# counter-defender-featherwing-mk-1_0.net
KiCad netlist of a schematic drawn in EAGLE
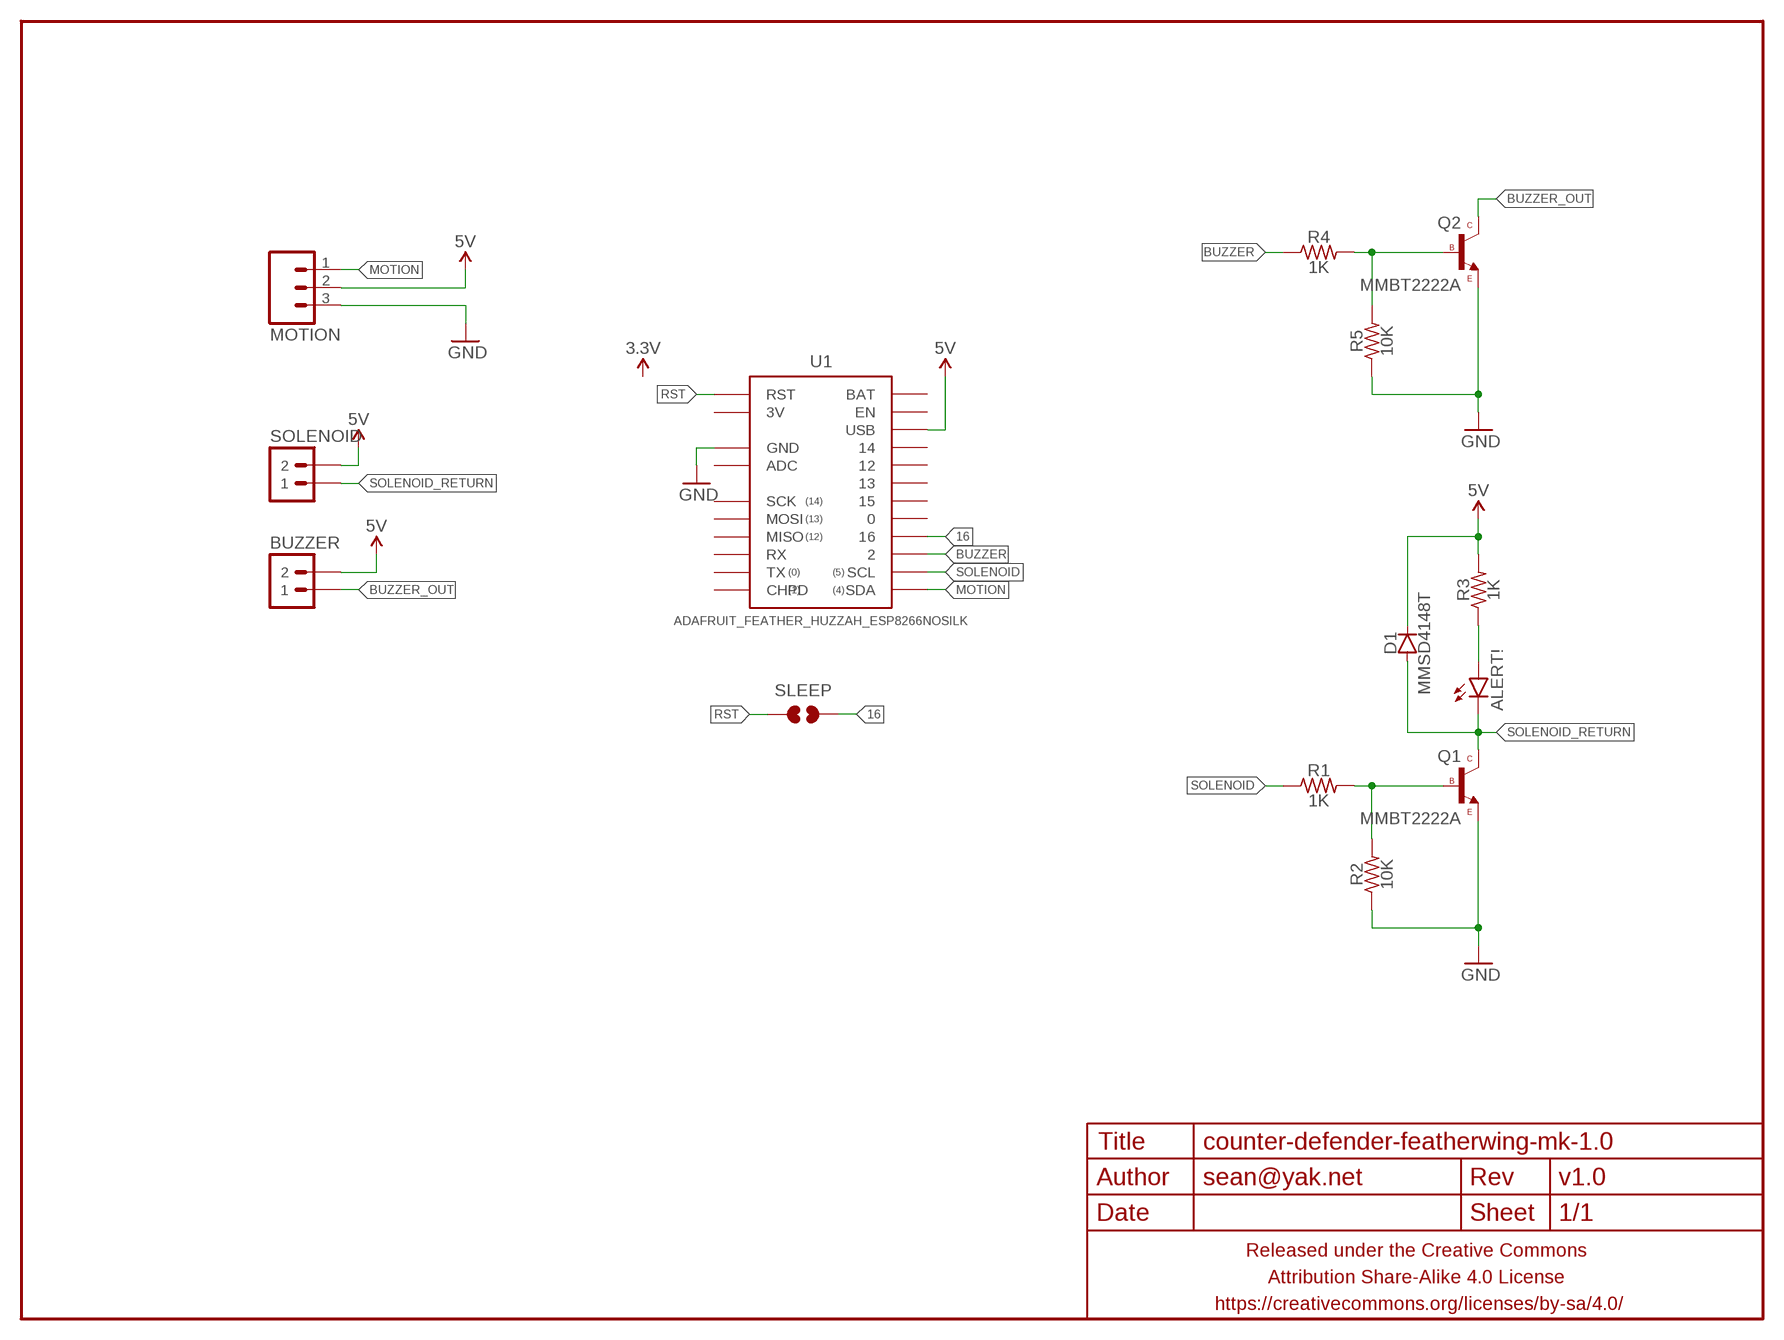
[diagram p0: schematic, sheet 1]

(export (version "E")
  (design (tool "Eeschema 10.0.6"))
  (components
    (comp (ref "ALERT!")
      (value "LED0603-TIGHT")
      (footprint "eagle-import:LED-0603-TIGHT")
      (libsource (lib "eagle-import") (part "LED0603-TIGHT"))
    )
    (comp (ref "BUZZER")
      (value "M02JST-PTH-RA-SMALLPADS")
      (footprint "eagle-import:JST-2-PH-RA-PTH-SMALLPADS")
      (libsource (lib "eagle-import") (part "M02JST-PTH-RA-SMALLPADS"))
    )
    (comp (ref "D1")
      (value "MMSD4148T")
      (footprint "eagle-import:SOD123")
      (libsource (lib "eagle-import") (part "DIODESOD123"))
    )
    (comp (ref "FRAME1")
      (value "FRAME-LETTERNO_PACKAGE")
      (footprint "eagle-import:DUMMY")
      (fields (field (name "DESIGNER") "sean@yak.net") (field (name "VERSION") "v1.0"))
      (libsource (lib "eagle-import") (part "FRAME-LETTERNO_PACKAGE"))
    )
    (comp (ref "MOTION")
      (value "M03JST-PTH")
      (footprint "eagle-import:JST-3-PH-RA-PTH")
      (libsource (lib "eagle-import") (part "M03JST-PTH"))
    )
    (comp (ref "Q1")
      (value "MMBT2222A")
      (footprint "eagle-import:SOT23")
      (libsource (lib "eagle-import") (part "TRANSISTOR_NPNMMBT2222A"))
    )
    (comp (ref "Q2")
      (value "MMBT2222A")
      (footprint "eagle-import:SOT23")
      (libsource (lib "eagle-import") (part "TRANSISTOR_NPNMMBT2222A"))
    )
    (comp (ref "R1")
      (value "1K")
      (footprint "eagle-import:R0603-TIGHTER")
      (libsource (lib "eagle-import") (part "RESISTORR0603-TIGHTER"))
    )
    (comp (ref "R2")
      (value "10K")
      (footprint "eagle-import:R0603-TIGHTER")
      (libsource (lib "eagle-import") (part "RESISTORR0603-TIGHTER"))
    )
    (comp (ref "R3")
      (value "1K")
      (footprint "eagle-import:R0603-TIGHTER")
      (libsource (lib "eagle-import") (part "RESISTORR0603-TIGHTER"))
    )
    (comp (ref "R4")
      (value "1K")
      (footprint "eagle-import:R0603-TIGHTER")
      (libsource (lib "eagle-import") (part "RESISTORR0603-TIGHTER"))
    )
    (comp (ref "R5")
      (value "10K")
      (footprint "eagle-import:R0603-TIGHTER")
      (libsource (lib "eagle-import") (part "RESISTORR0603-TIGHTER"))
    )
    (comp (ref "SLEEP")
      (value "JUMPER-PAD-2-NOYES_SILK")
      (footprint "eagle-import:PAD-JUMPER-2-NO_YES_SILK")
      (libsource (lib "eagle-import") (part "JUMPER-PAD-2-NOYES_SILK"))
    )
    (comp (ref "SOLENOID")
      (value "M02JST-PTH-RA-SMALLPADS")
      (footprint "eagle-import:JST-2-PH-RA-PTH-SMALLPADS")
      (libsource (lib "eagle-import") (part "M02JST-PTH-RA-SMALLPADS"))
    )
    (comp (ref "U1")
      (value "ADAFRUIT_FEATHER_HUZZAH_ESP8266NOSILK")
      (footprint "eagle-import:ADAFRUIT_FEATHER_HUZZAH_NOSILK")
      (libsource (lib "eagle-import") (part "ADAFRUIT_FEATHER_HUZZAH_ESP8266NOSILK"))
    )
  )
  (nets
    (net (code "2") (name "5V") (class "Default")
      (node (ref "BUZZER") (pin "2") (pinfunction "2_2") (pintype "passive"))
      (node (ref "D1") (pin "C") (pinfunction "C_C") (pintype "passive"))
      (node (ref "MOTION") (pin "2") (pinfunction "2_2") (pintype "passive"))
      (node (ref "R3") (pin "2") (pinfunction "2_2") (pintype "passive"))
      (node (ref "SOLENOID") (pin "2") (pinfunction "2_2") (pintype "passive"))
      (node (ref "U1") (pin "USB") (pinfunction "USB_USB") (pintype "bidirectional"))
    )
    (net (code "3") (name "16") (class "Default")
      (node (ref "SLEEP") (pin "2") (pinfunction "2_2") (pintype "passive"))
      (node (ref "U1") (pin "16") (pinfunction "16_16") (pintype "bidirectional"))
    )
    (net (code "4") (name "BUZZER") (class "Default")
      (node (ref "R4") (pin "1") (pinfunction "1_1") (pintype "passive"))
      (node (ref "U1") (pin "2") (pinfunction "2_2") (pintype "bidirectional"))
    )
    (net (code "5") (name "BUZZER_OUT") (class "Default")
      (node (ref "BUZZER") (pin "1") (pinfunction "1_1") (pintype "passive"))
      (node (ref "Q2") (pin "3") (pinfunction "C_3") (pintype "passive"))
    )
    (net (code "6") (name "GND") (class "Default")
      (node (ref "MOTION") (pin "3") (pinfunction "3_3") (pintype "passive"))
      (node (ref "Q1") (pin "2") (pinfunction "E_2") (pintype "passive"))
      (node (ref "Q2") (pin "2") (pinfunction "E_2") (pintype "passive"))
      (node (ref "R2") (pin "1") (pinfunction "1_1") (pintype "passive"))
      (node (ref "R5") (pin "1") (pinfunction "1_1") (pintype "passive"))
      (node (ref "U1") (pin "GND@0") (pinfunction "GND_GND@0") (pintype "bidirectional"))
    )
    (net (code "7") (name "MOTION") (class "Default")
      (node (ref "MOTION") (pin "1") (pinfunction "1_1") (pintype "passive"))
      (node (ref "U1") (pin "SDA") (pinfunction "SDA_SDA") (pintype "bidirectional"))
    )
    (net (code "8") (name "Net-(ALERT!-PadA)") (class "Default")
      (node (ref "ALERT!") (pin "A") (pinfunction "A_A") (pintype "passive"))
      (node (ref "R3") (pin "1") (pinfunction "1_1") (pintype "passive"))
    )
    (net (code "9") (name "Net-(Q1-B)") (class "Default")
      (node (ref "Q1") (pin "1") (pinfunction "B_1") (pintype "passive"))
      (node (ref "R1") (pin "2") (pinfunction "2_2") (pintype "passive"))
      (node (ref "R2") (pin "2") (pinfunction "2_2") (pintype "passive"))
    )
    (net (code "10") (name "Net-(Q2-B)") (class "Default")
      (node (ref "Q2") (pin "1") (pinfunction "B_1") (pintype "passive"))
      (node (ref "R4") (pin "2") (pinfunction "2_2") (pintype "passive"))
      (node (ref "R5") (pin "2") (pinfunction "2_2") (pintype "passive"))
    )
    (net (code "11") (name "RST") (class "Default")
      (node (ref "SLEEP") (pin "1") (pinfunction "1_1") (pintype "passive"))
      (node (ref "U1") (pin "RST") (pinfunction "RST_RST") (pintype "bidirectional"))
    )
    (net (code "12") (name "SOLENOID") (class "Default")
      (node (ref "R1") (pin "1") (pinfunction "1_1") (pintype "passive"))
      (node (ref "U1") (pin "SCL") (pinfunction "SCL_SCL") (pintype "bidirectional"))
    )
    (net (code "13") (name "SOLENOID_RETURN") (class "Default")
      (node (ref "ALERT!") (pin "C") (pinfunction "C_C") (pintype "passive"))
      (node (ref "D1") (pin "A") (pinfunction "A_A") (pintype "passive"))
      (node (ref "Q1") (pin "3") (pinfunction "C_3") (pintype "passive"))
      (node (ref "SOLENOID") (pin "1") (pinfunction "1_1") (pintype "passive"))
    )
    (net (code "14") (name "unconnected-(U1-Pad0)") (class "Default")
      (node (ref "U1") (pin "0") (pinfunction "0_0") (pintype "bidirectional"))
    )
    (net (code "15") (name "unconnected-(U1-Pad3V)") (class "Default")
      (node (ref "U1") (pin "3V") (pinfunction "3V_3V") (pintype "bidirectional"))
    )
    (net (code "16") (name "unconnected-(U1-Pad12)") (class "Default")
      (node (ref "U1") (pin "12") (pinfunction "12_12") (pintype "bidirectional"))
    )
    (net (code "17") (name "unconnected-(U1-Pad13)") (class "Default")
      (node (ref "U1") (pin "13") (pinfunction "13_13") (pintype "bidirectional"))
    )
    (net (code "18") (name "unconnected-(U1-Pad14)") (class "Default")
      (node (ref "U1") (pin "14") (pinfunction "14_14") (pintype "bidirectional"))
    )
    (net (code "19") (name "unconnected-(U1-Pad15)") (class "Default")
      (node (ref "U1") (pin "15") (pinfunction "15_15") (pintype "bidirectional"))
    )
    (net (code "20") (name "unconnected-(U1-PadADC)") (class "Default")
      (node (ref "U1") (pin "ADC") (pinfunction "ADC_ADC") (pintype "bidirectional"))
    )
    (net (code "21") (name "unconnected-(U1-PadBAT)") (class "Default")
      (node (ref "U1") (pin "BAT") (pinfunction "BAT_BAT") (pintype "bidirectional"))
    )
    (net (code "22") (name "unconnected-(U1-PadCHPD)") (class "Default")
      (node (ref "U1") (pin "CHPD") (pinfunction "CHPD_CHPD") (pintype "bidirectional"))
    )
    (net (code "23") (name "unconnected-(U1-PadEN)") (class "Default")
      (node (ref "U1") (pin "EN") (pinfunction "EN_EN") (pintype "bidirectional"))
    )
    (net (code "24") (name "unconnected-(U1-PadMISO)") (class "Default")
      (node (ref "U1") (pin "MISO") (pinfunction "MISO_MISO") (pintype "bidirectional"))
    )
    (net (code "25") (name "unconnected-(U1-PadMOSI)") (class "Default")
      (node (ref "U1") (pin "MOSI") (pinfunction "MOSI_MOSI") (pintype "bidirectional"))
    )
    (net (code "26") (name "unconnected-(U1-PadRX)") (class "Default")
      (node (ref "U1") (pin "RX") (pinfunction "RX_RX") (pintype "bidirectional"))
    )
    (net (code "27") (name "unconnected-(U1-PadSCK)") (class "Default")
      (node (ref "U1") (pin "SCK") (pinfunction "SCK_SCK") (pintype "bidirectional"))
    )
    (net (code "28") (name "unconnected-(U1-PadTX)") (class "Default")
      (node (ref "U1") (pin "TX") (pinfunction "TX_TX") (pintype "bidirectional"))
    )
  )
)
